# Schematic_Equipment_control_and_gateway_.net
KiCad netlist of a schematic drawn in EasyEDA
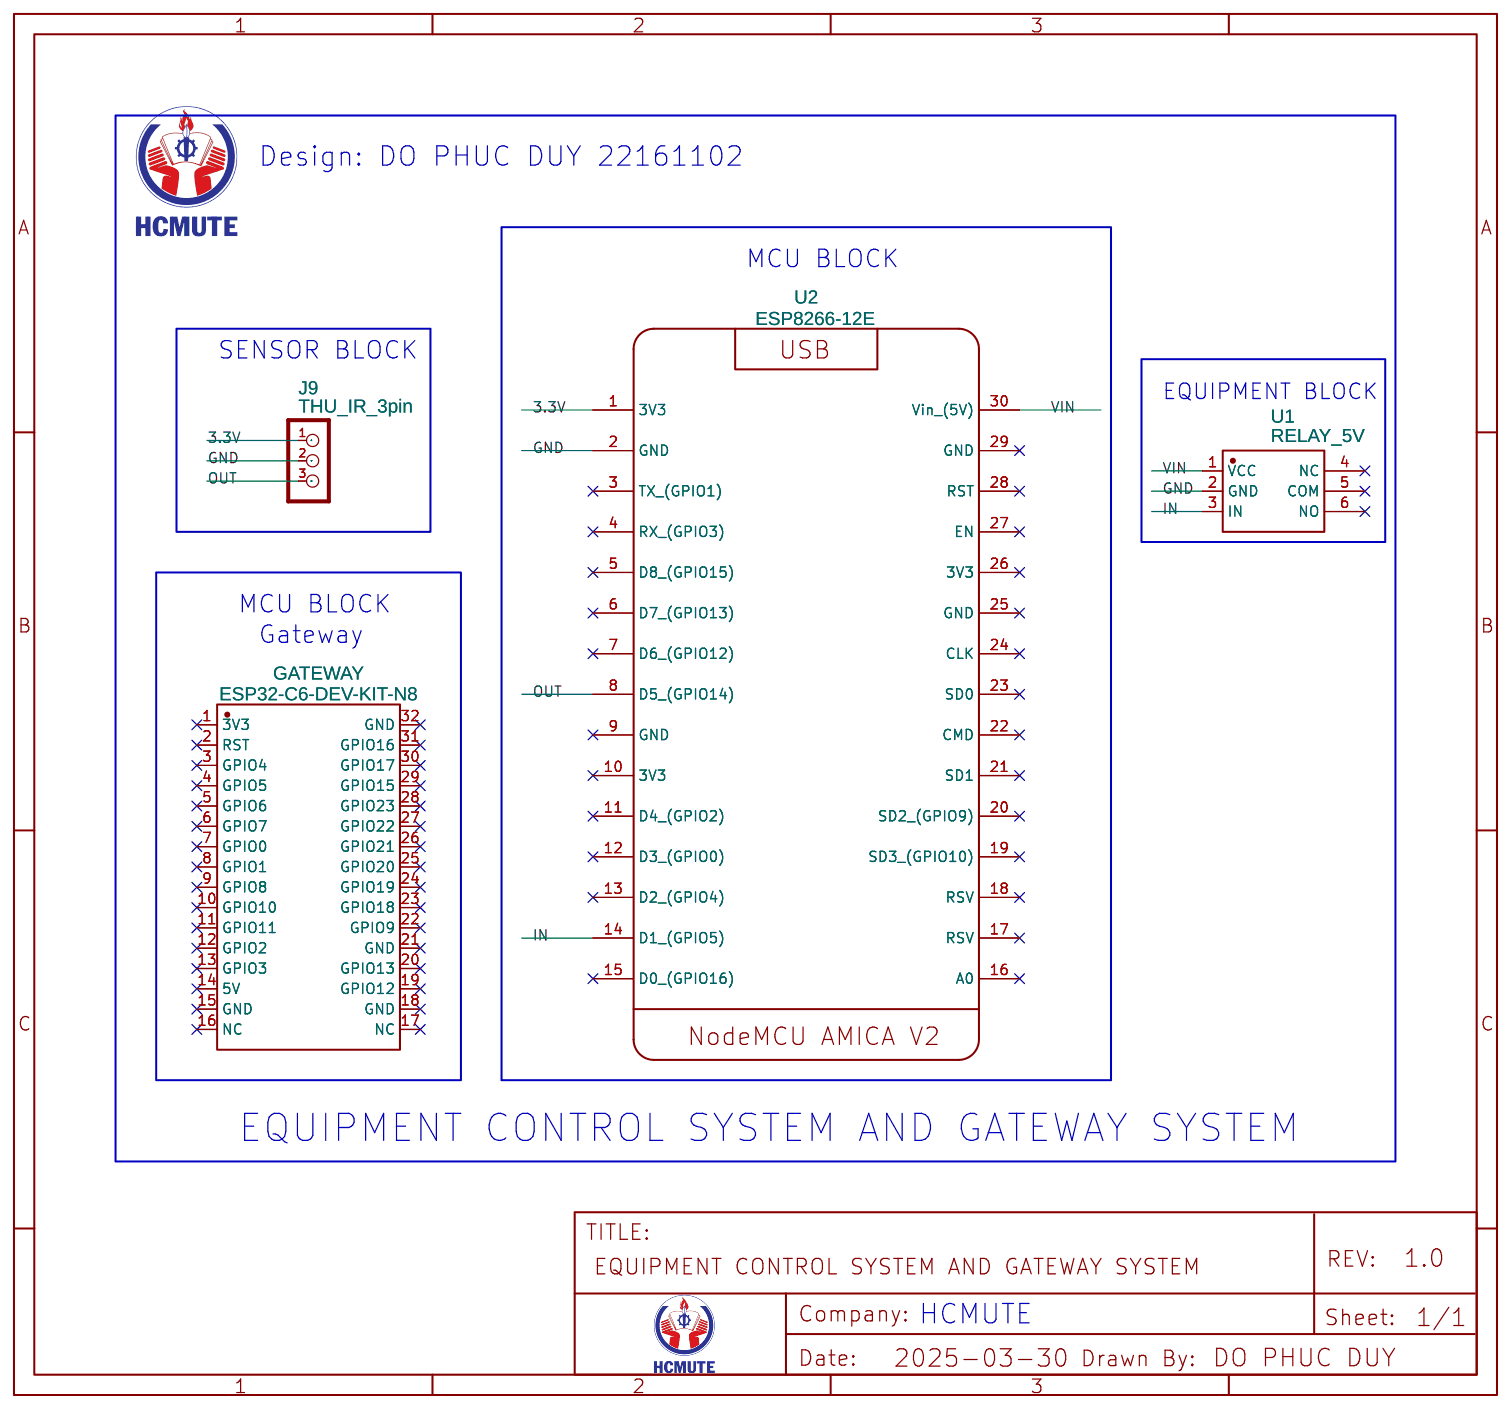
[diagram p0: schematic sheet]

(export (version "E")
  (design (tool "Eeschema 10.0.6"))
  (components
    (comp (ref "GATEWAY") (value "ESP32-C6-DEV-KIT-N8") (libsource (lib "") (part "ESP32-C6-DEV-KIT-N8")))
    (comp (ref "J9") (value "THU_IR_3pin") (libsource (lib "") (part "CON_HEADER_1X03")))
    (comp (ref "U1")
      (value "RELAY_5V")
      (fields (field (name "Manufacturer Part") "Monday Kids") (field (name "Manufacturer") "China"))
      (libsource (lib "") (part "RELAY_5V"))
    )
    (comp (ref "U2") (value "ESP8266-12E") (libsource (lib "") (part "ESP8266-12E")))
  )
  (nets
    (net (code "1") (name "/3.3V") (class "Default")
      (node (ref "J9") (pin "1") (pinfunction "1_1") (pintype "unspecified"))
      (node (ref "U2") (pin "1") (pinfunction "3V3_1") (pintype "unspecified"))
    )
    (net (code "2") (name "/GND") (class "Default")
      (node (ref "J9") (pin "2") (pinfunction "2_2") (pintype "unspecified"))
      (node (ref "U1") (pin "2") (pinfunction "GND_2") (pintype "unspecified"))
      (node (ref "U2") (pin "2") (pinfunction "GND_2") (pintype "unspecified"))
    )
    (net (code "3") (name "/IN") (class "Default")
      (node (ref "U1") (pin "3") (pinfunction "IN_3") (pintype "unspecified"))
      (node (ref "U2") (pin "14") (pinfunction "D1_(GPIO5)_14") (pintype "unspecified"))
    )
    (net (code "4") (name "/OUT") (class "Default")
      (node (ref "J9") (pin "3") (pinfunction "3_3") (pintype "unspecified"))
      (node (ref "U2") (pin "8") (pinfunction "D5_(GPIO14)_8") (pintype "unspecified"))
    )
    (net (code "5") (name "/VIN") (class "Default")
      (node (ref "U1") (pin "1") (pinfunction "VCC_1") (pintype "unspecified"))
      (node (ref "U2") (pin "30") (pinfunction "Vin_(5V)_30") (pintype "unspecified"))
    )
    (net (code "6") (name "unconnected-(GATEWAY-3V3-Pad1)") (class "Default")
      (node (ref "GATEWAY") (pin "1") (pinfunction "3V3_1") (pintype "unspecified+no_connect"))
    )
    (net (code "7") (name "unconnected-(GATEWAY-5V-Pad14)") (class "Default")
      (node (ref "GATEWAY") (pin "14") (pinfunction "5V_14") (pintype "unspecified+no_connect"))
    )
    (net (code "8") (name "unconnected-(GATEWAY-GND-Pad15)") (class "Default")
      (node (ref "GATEWAY") (pin "15") (pinfunction "GND_15") (pintype "unspecified+no_connect"))
    )
    (net (code "9") (name "unconnected-(GATEWAY-GND-Pad18)") (class "Default")
      (node (ref "GATEWAY") (pin "18") (pinfunction "GND_18") (pintype "unspecified+no_connect"))
    )
    (net (code "10") (name "unconnected-(GATEWAY-GND-Pad21)") (class "Default")
      (node (ref "GATEWAY") (pin "21") (pinfunction "GND_21") (pintype "unspecified+no_connect"))
    )
    (net (code "11") (name "unconnected-(GATEWAY-GND-Pad32)") (class "Default")
      (node (ref "GATEWAY") (pin "32") (pinfunction "GND_32") (pintype "unspecified+no_connect"))
    )
    (net (code "12") (name "unconnected-(GATEWAY-GPIO0-Pad7)") (class "Default")
      (node (ref "GATEWAY") (pin "7") (pinfunction "GPIO0_7") (pintype "unspecified+no_connect"))
    )
    (net (code "13") (name "unconnected-(GATEWAY-GPIO1-Pad8)") (class "Default")
      (node (ref "GATEWAY") (pin "8") (pinfunction "GPIO1_8") (pintype "unspecified+no_connect"))
    )
    (net (code "14") (name "unconnected-(GATEWAY-GPIO2-Pad12)") (class "Default")
      (node (ref "GATEWAY") (pin "12") (pinfunction "GPIO2_12") (pintype "unspecified+no_connect"))
    )
    (net (code "15") (name "unconnected-(GATEWAY-GPIO3-Pad13)") (class "Default")
      (node (ref "GATEWAY") (pin "13") (pinfunction "GPIO3_13") (pintype "unspecified+no_connect"))
    )
    (net (code "16") (name "unconnected-(GATEWAY-GPIO4-Pad3)") (class "Default")
      (node (ref "GATEWAY") (pin "3") (pinfunction "GPIO4_3") (pintype "unspecified+no_connect"))
    )
    (net (code "17") (name "unconnected-(GATEWAY-GPIO5-Pad4)") (class "Default")
      (node (ref "GATEWAY") (pin "4") (pinfunction "GPIO5_4") (pintype "unspecified+no_connect"))
    )
    (net (code "18") (name "unconnected-(GATEWAY-GPIO6-Pad5)") (class "Default")
      (node (ref "GATEWAY") (pin "5") (pinfunction "GPIO6_5") (pintype "unspecified+no_connect"))
    )
    (net (code "19") (name "unconnected-(GATEWAY-GPIO7-Pad6)") (class "Default")
      (node (ref "GATEWAY") (pin "6") (pinfunction "GPIO7_6") (pintype "unspecified+no_connect"))
    )
    (net (code "20") (name "unconnected-(GATEWAY-GPIO8-Pad9)") (class "Default")
      (node (ref "GATEWAY") (pin "9") (pinfunction "GPIO8_9") (pintype "unspecified+no_connect"))
    )
    (net (code "21") (name "unconnected-(GATEWAY-GPIO9-Pad22)") (class "Default")
      (node (ref "GATEWAY") (pin "22") (pinfunction "GPIO9_22") (pintype "unspecified+no_connect"))
    )
    (net (code "22") (name "unconnected-(GATEWAY-GPIO10-Pad10)") (class "Default")
      (node (ref "GATEWAY") (pin "10") (pinfunction "GPIO10_10") (pintype "unspecified+no_connect"))
    )
    (net (code "23") (name "unconnected-(GATEWAY-GPIO11-Pad11)") (class "Default")
      (node (ref "GATEWAY") (pin "11") (pinfunction "GPIO11_11") (pintype "unspecified+no_connect"))
    )
    (net (code "24") (name "unconnected-(GATEWAY-GPIO12-Pad19)") (class "Default")
      (node (ref "GATEWAY") (pin "19") (pinfunction "GPIO12_19") (pintype "unspecified+no_connect"))
    )
    (net (code "25") (name "unconnected-(GATEWAY-GPIO13-Pad20)") (class "Default")
      (node (ref "GATEWAY") (pin "20") (pinfunction "GPIO13_20") (pintype "unspecified+no_connect"))
    )
    (net (code "26") (name "unconnected-(GATEWAY-GPIO15-Pad29)") (class "Default")
      (node (ref "GATEWAY") (pin "29") (pinfunction "GPIO15_29") (pintype "unspecified+no_connect"))
    )
    (net (code "27") (name "unconnected-(GATEWAY-GPIO16-Pad31)") (class "Default")
      (node (ref "GATEWAY") (pin "31") (pinfunction "GPIO16_31") (pintype "unspecified+no_connect"))
    )
    (net (code "28") (name "unconnected-(GATEWAY-GPIO17-Pad30)") (class "Default")
      (node (ref "GATEWAY") (pin "30") (pinfunction "GPIO17_30") (pintype "unspecified+no_connect"))
    )
    (net (code "29") (name "unconnected-(GATEWAY-GPIO18-Pad23)") (class "Default")
      (node (ref "GATEWAY") (pin "23") (pinfunction "GPIO18_23") (pintype "unspecified+no_connect"))
    )
    (net (code "30") (name "unconnected-(GATEWAY-GPIO19-Pad24)") (class "Default")
      (node (ref "GATEWAY") (pin "24") (pinfunction "GPIO19_24") (pintype "unspecified+no_connect"))
    )
    (net (code "31") (name "unconnected-(GATEWAY-GPIO20-Pad25)") (class "Default")
      (node (ref "GATEWAY") (pin "25") (pinfunction "GPIO20_25") (pintype "unspecified+no_connect"))
    )
    (net (code "32") (name "unconnected-(GATEWAY-GPIO21-Pad26)") (class "Default")
      (node (ref "GATEWAY") (pin "26") (pinfunction "GPIO21_26") (pintype "unspecified+no_connect"))
    )
    (net (code "33") (name "unconnected-(GATEWAY-GPIO22-Pad27)") (class "Default")
      (node (ref "GATEWAY") (pin "27") (pinfunction "GPIO22_27") (pintype "unspecified+no_connect"))
    )
    (net (code "34") (name "unconnected-(GATEWAY-GPIO23-Pad28)") (class "Default")
      (node (ref "GATEWAY") (pin "28") (pinfunction "GPIO23_28") (pintype "unspecified+no_connect"))
    )
    (net (code "35") (name "unconnected-(GATEWAY-NC-Pad16)") (class "Default")
      (node (ref "GATEWAY") (pin "16") (pinfunction "NC_16") (pintype "unspecified+no_connect"))
    )
    (net (code "36") (name "unconnected-(GATEWAY-NC-Pad17)") (class "Default")
      (node (ref "GATEWAY") (pin "17") (pinfunction "NC_17") (pintype "unspecified+no_connect"))
    )
    (net (code "37") (name "unconnected-(GATEWAY-RST-Pad2)") (class "Default")
      (node (ref "GATEWAY") (pin "2") (pinfunction "RST_2") (pintype "unspecified+no_connect"))
    )
    (net (code "38") (name "unconnected-(U1-COM-Pad5)") (class "Default")
      (node (ref "U1") (pin "5") (pinfunction "COM_5") (pintype "unspecified+no_connect"))
    )
    (net (code "39") (name "unconnected-(U1-NC-Pad4)") (class "Default")
      (node (ref "U1") (pin "4") (pinfunction "NC_4") (pintype "unspecified+no_connect"))
    )
    (net (code "40") (name "unconnected-(U1-NO-Pad6)") (class "Default")
      (node (ref "U1") (pin "6") (pinfunction "NO_6") (pintype "unspecified+no_connect"))
    )
    (net (code "41") (name "unconnected-(U2-3V3-Pad10)") (class "Default")
      (node (ref "U2") (pin "10") (pinfunction "3V3_10") (pintype "unspecified+no_connect"))
    )
    (net (code "42") (name "unconnected-(U2-3V3-Pad26)") (class "Default")
      (node (ref "U2") (pin "26") (pinfunction "3V3_26") (pintype "unspecified+no_connect"))
    )
    (net (code "43") (name "unconnected-(U2-A0-Pad16)") (class "Default")
      (node (ref "U2") (pin "16") (pinfunction "A0_16") (pintype "unspecified+no_connect"))
    )
    (net (code "44") (name "unconnected-(U2-CLK-Pad24)") (class "Default")
      (node (ref "U2") (pin "24") (pinfunction "CLK_24") (pintype "unspecified+no_connect"))
    )
    (net (code "45") (name "unconnected-(U2-CMD-Pad22)") (class "Default")
      (node (ref "U2") (pin "22") (pinfunction "CMD_22") (pintype "unspecified+no_connect"))
    )
    (net (code "46") (name "unconnected-(U2-D0_(GPIO16)-Pad15)") (class "Default")
      (node (ref "U2") (pin "15") (pinfunction "D0_(GPIO16)_15") (pintype "unspecified+no_connect"))
    )
    (net (code "47") (name "unconnected-(U2-D2_(GPIO4)-Pad13)") (class "Default")
      (node (ref "U2") (pin "13") (pinfunction "D2_(GPIO4)_13") (pintype "unspecified+no_connect"))
    )
    (net (code "48") (name "unconnected-(U2-D3_(GPIO0)-Pad12)") (class "Default")
      (node (ref "U2") (pin "12") (pinfunction "D3_(GPIO0)_12") (pintype "unspecified+no_connect"))
    )
    (net (code "49") (name "unconnected-(U2-D4_(GPIO2)-Pad11)") (class "Default")
      (node (ref "U2") (pin "11") (pinfunction "D4_(GPIO2)_11") (pintype "unspecified+no_connect"))
    )
    (net (code "50") (name "unconnected-(U2-D6_(GPIO12)-Pad7)") (class "Default")
      (node (ref "U2") (pin "7") (pinfunction "D6_(GPIO12)_7") (pintype "unspecified+no_connect"))
    )
    (net (code "51") (name "unconnected-(U2-D7_(GPIO13)-Pad6)") (class "Default")
      (node (ref "U2") (pin "6") (pinfunction "D7_(GPIO13)_6") (pintype "unspecified+no_connect"))
    )
    (net (code "52") (name "unconnected-(U2-D8_(GPIO15)-Pad5)") (class "Default")
      (node (ref "U2") (pin "5") (pinfunction "D8_(GPIO15)_5") (pintype "unspecified+no_connect"))
    )
    (net (code "53") (name "unconnected-(U2-EN-Pad27)") (class "Default")
      (node (ref "U2") (pin "27") (pinfunction "EN_27") (pintype "unspecified+no_connect"))
    )
    (net (code "54") (name "unconnected-(U2-GND-Pad9)") (class "Default")
      (node (ref "U2") (pin "9") (pinfunction "GND_9") (pintype "unspecified+no_connect"))
    )
    (net (code "55") (name "unconnected-(U2-GND-Pad25)") (class "Default")
      (node (ref "U2") (pin "25") (pinfunction "GND_25") (pintype "unspecified+no_connect"))
    )
    (net (code "56") (name "unconnected-(U2-GND-Pad29)") (class "Default")
      (node (ref "U2") (pin "29") (pinfunction "GND_29") (pintype "unspecified+no_connect"))
    )
    (net (code "57") (name "unconnected-(U2-RST-Pad28)") (class "Default")
      (node (ref "U2") (pin "28") (pinfunction "RST_28") (pintype "unspecified+no_connect"))
    )
    (net (code "58") (name "unconnected-(U2-RSV-Pad17)") (class "Default")
      (node (ref "U2") (pin "17") (pinfunction "RSV_17") (pintype "unspecified+no_connect"))
    )
    (net (code "59") (name "unconnected-(U2-RSV-Pad18)") (class "Default")
      (node (ref "U2") (pin "18") (pinfunction "RSV_18") (pintype "unspecified+no_connect"))
    )
    (net (code "60") (name "unconnected-(U2-RX_(GPIO3)-Pad4)") (class "Default")
      (node (ref "U2") (pin "4") (pinfunction "RX_(GPIO3)_4") (pintype "unspecified+no_connect"))
    )
    (net (code "61") (name "unconnected-(U2-SD0-Pad23)") (class "Default")
      (node (ref "U2") (pin "23") (pinfunction "SD0_23") (pintype "unspecified+no_connect"))
    )
    (net (code "62") (name "unconnected-(U2-SD1-Pad21)") (class "Default")
      (node (ref "U2") (pin "21") (pinfunction "SD1_21") (pintype "unspecified+no_connect"))
    )
    (net (code "63") (name "unconnected-(U2-SD2_(GPIO9)-Pad20)") (class "Default")
      (node (ref "U2") (pin "20") (pinfunction "SD2_(GPIO9)_20") (pintype "unspecified+no_connect"))
    )
    (net (code "64") (name "unconnected-(U2-SD3_(GPIO10)-Pad19)") (class "Default")
      (node (ref "U2") (pin "19") (pinfunction "SD3_(GPIO10)_19") (pintype "unspecified+no_connect"))
    )
    (net (code "65") (name "unconnected-(U2-TX_(GPIO1)-Pad3)") (class "Default")
      (node (ref "U2") (pin "3") (pinfunction "TX_(GPIO1)_3") (pintype "unspecified+no_connect"))
    )
  )
)
